# fonte_chaveada.net
KiCad netlist of a schematic drawn in Altium Designer
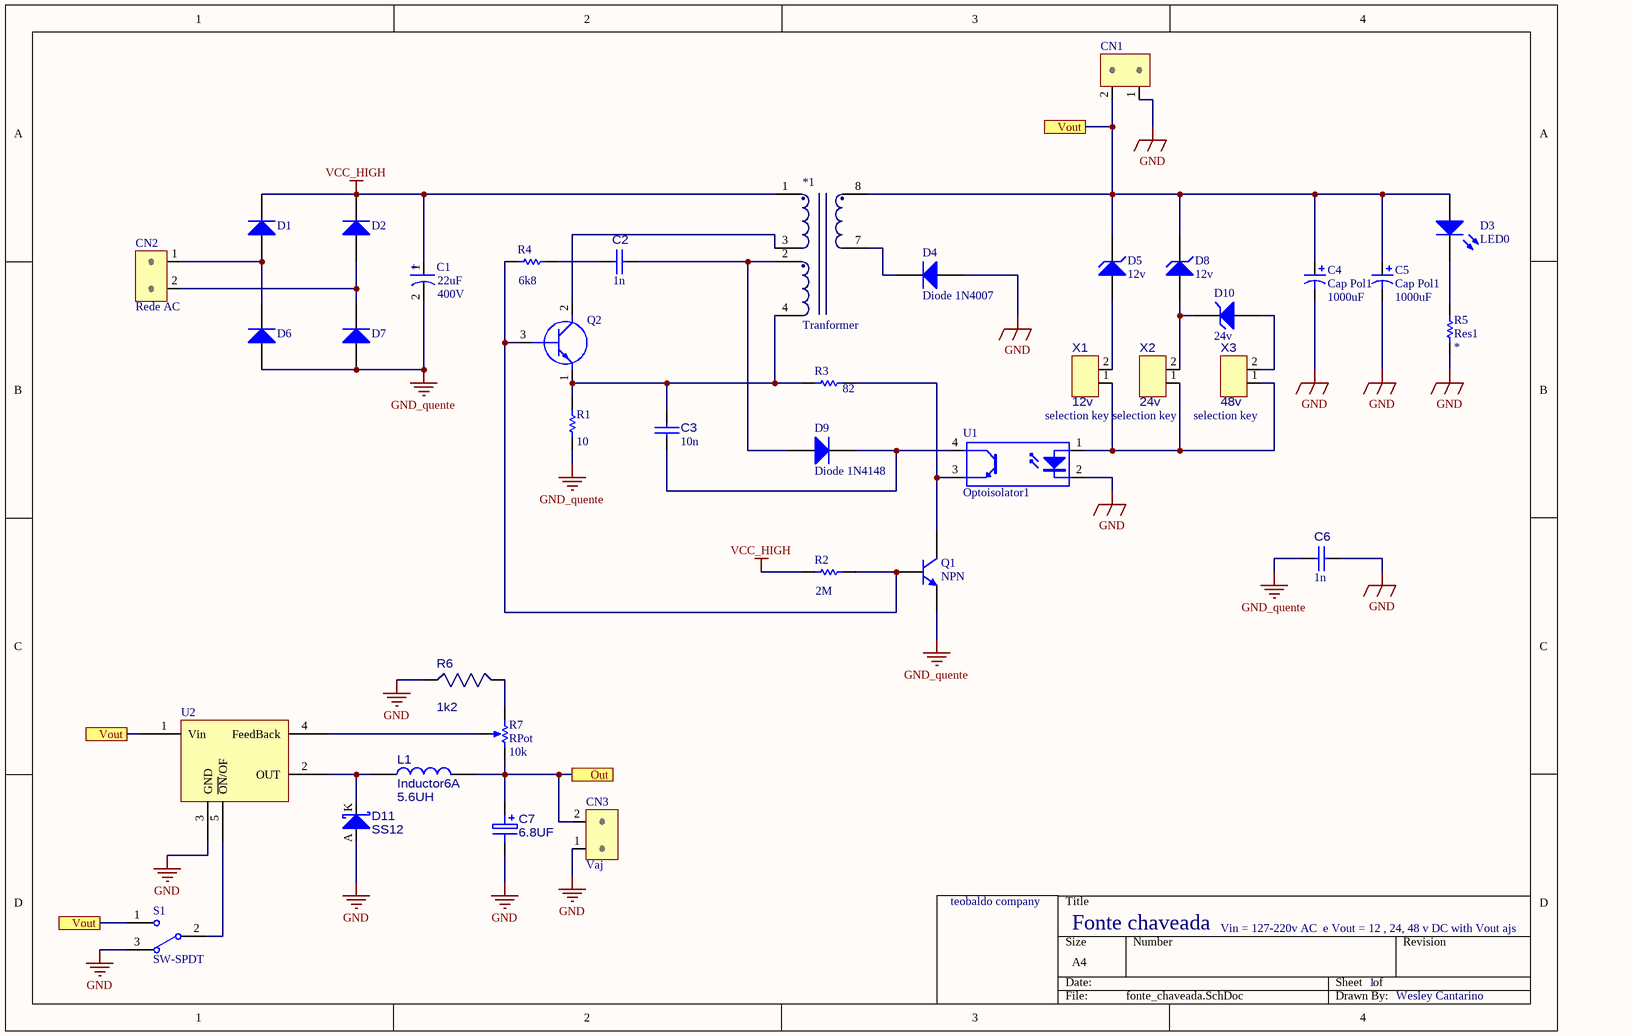
[diagram p0: fonte_chaveada.SchDoc]

(export (version "E")
  (design (tool "Eeschema 10.0.6"))
  (components
    (comp (ref "*1")
      (value "Tranformer")
      (footprint "DIV_TRAFO PLC")
      (libsource (lib "i9Library_Altium") (part "Tranformer PLC"))
    )
    (comp (ref "C1")
      (value "22uF")
      (footprint "CAP_ALU_RADIAL_7.5mm")
      (description "PTH Radial Electrolytic Capacitor")
      (fields (field (name "TENSÃO") "400V") (field (name "Comment") "Electrolytic Capacitor"))
      (libsource (lib "i9Library_Altium") (part "CAP_ALU_RADIAL_7.5MM"))
    )
    (comp (ref "C2")
      (value "1n")
      (footprint "CAP_CER_RADIAL_3.5MM")
      (description "PTH Radial Ceramic Capacitor")
      (libsource (lib "i9Library_Altium") (part "CAP_CER_RADIAL_3.5MM"))
    )
    (comp (ref "C3")
      (value "10n")
      (footprint "CAP_CER_RADIAL_3.5MM")
      (description "PTH Radial Ceramic Capacitor")
      (libsource (lib "i9Library_Altium") (part "CAP_CER_RADIAL_3.5MM"))
    )
    (comp (ref "C4")
      (value "Cap Pol1")
      (footprint "RB7.6-15")
      (description "Polarized Capacitor (Radial)")
      (fields (field (name "ALTIUM_VALUE") "1000uF") (field (name "PUBLISHER") "Altium Limited"))
      (libsource (lib "Miscellaneous Devices") (part "Cap Pol1"))
    )
    (comp (ref "C5")
      (value "Cap Pol1")
      (footprint "RB7.6-15")
      (description "Polarized Capacitor (Radial)")
      (fields (field (name "ALTIUM_VALUE") "1000uF") (field (name "PUBLISHER") "Altium Limited"))
      (libsource (lib "Miscellaneous Devices") (part "Cap Pol1"))
    )
    (comp (ref "C6")
      (value "1n")
      (footprint "CAP_CER_RADIAL_3.5MM")
      (description "PTH Radial Ceramic Capacitor")
      (libsource (lib "i9Library_Altium") (part "CAP_CER_RADIAL_3.5MM"))
    )
    (comp (ref "C7")
      (value "6.8UF")
      (footprint "RADPOL8X11")
      (libsource (lib "i9Library_v1.7.5") (part "ELECTRO1_1"))
    )
    (comp (ref "CN1")
      (value "Vout")
      (footprint "MKDSN02")
      (description "MKDS")
      (libsource (lib "") (part "CN_2_1"))
    )
    (comp (ref "CN2")
      (value "Rede AC")
      (footprint "MKDSN02")
      (description "MKDS")
      (libsource (lib "i9Library_v1.7.5") (part "CN_2"))
    )
    (comp (ref "CN3")
      (value "Vaj")
      (footprint "CN_KRE_2")
      (description "MKDS_2")
      (libsource (lib "i9Library_Altium") (part "CN_MKDS_2"))
    )
    (comp (ref "D1")
      (value "Diode 1N4007")
      (footprint "DO-41")
      (description "1 Amp General Purpose Rectifier")
      (fields (field (name "PUBLISHER") "Altium Limited"))
      (libsource (lib "Miscellaneous Devices") (part "Diode 1N4007"))
    )
    (comp (ref "D2")
      (value "Diode 1N4007")
      (footprint "DO-41")
      (description "1 Amp General Purpose Rectifier")
      (fields (field (name "PUBLISHER") "Altium Limited"))
      (libsource (lib "Miscellaneous Devices") (part "Diode 1N4007"))
    )
    (comp (ref "D3")
      (value "LED0")
      (footprint "LED-0")
      (description "Typical INFRARED GaAs LED")
      (fields (field (name "PUBLISHER") "Altium Limited"))
      (libsource (lib "Miscellaneous Devices") (part "LED0"))
    )
    (comp (ref "D4")
      (value "Diode 1N4007")
      (footprint "DO-41")
      (description "1 Amp General Purpose Rectifier")
      (fields (field (name "PUBLISHER") "Altium Limited"))
      (libsource (lib "Miscellaneous Devices") (part "Diode 1N4007"))
    )
    (comp (ref "D5")
      (value "12v")
      (footprint "DIO_PTH_5MM")
      (description "Zener Diode")
      (fields (field (name "PUBLISHER") "Altium Limited"))
      (libsource (lib "Miscellaneous Devices") (part "D Zener"))
    )
    (comp (ref "D6")
      (value "Diode 1N4007")
      (footprint "DO-41")
      (description "1 Amp General Purpose Rectifier")
      (fields (field (name "PUBLISHER") "Altium Limited"))
      (libsource (lib "Miscellaneous Devices") (part "Diode 1N4007"))
    )
    (comp (ref "D7")
      (value "Diode 1N4007")
      (footprint "DO-41")
      (description "1 Amp General Purpose Rectifier")
      (fields (field (name "PUBLISHER") "Altium Limited"))
      (libsource (lib "Miscellaneous Devices") (part "Diode 1N4007"))
    )
    (comp (ref "D8")
      (value "12v")
      (footprint "DIO_PTH_5MM")
      (description "Zener Diode")
      (fields (field (name "PUBLISHER") "Altium Limited"))
      (libsource (lib "Miscellaneous Devices") (part "D Zener"))
    )
    (comp (ref "D9")
      (value "Diode 1N4148")
      (footprint "DO-41")
      (description "1 Amp General Purpose Rectifier")
      (fields (field (name "PUBLISHER") "Altium Limited"))
      (libsource (lib "Miscellaneous Devices") (part "Diode 1N4007"))
    )
    (comp (ref "D10")
      (value "24v")
      (footprint "DIO_PTH_5MM")
      (description "Zener Diode")
      (fields (field (name "PUBLISHER") "Altium Limited"))
      (libsource (lib "Miscellaneous Devices") (part "D Zener"))
    )
    (comp (ref "D11")
      (value "SS12")
      (footprint "DIO_PTH_5MM")
      (description "Schottky Diode")
      (fields
        (field (name "DIGIKEY PART NUMBER") "SS12E-TPMSCT-ND")
        (field (name "Comment") "DIODE - SCHOTTKY")
      )
      (libsource (lib "i9Library_v1.7.5") (part "DIODE - SCHOTTKY"))
    )
    (comp (ref "L1")
      (value "5.6UH")
      (footprint "Inductor6A")
      (description "FIXED IND 5.6UH 6A 14.4 MOHM SMD")
      (libsource (lib "i9Library_v1.7.5") (part "IND_1"))
    )
    (comp (ref "Q1")
      (value "NPN")
      (footprint "TO-226-AA")
      (description "NPN Bipolar Transistor")
      (fields (field (name "PUBLISHER") "Altium Limited"))
      (libsource (lib "Miscellaneous Devices") (part "NPN"))
    )
    (comp (ref "Q2")
      (value "BD135")
      (footprint "SamacSys:TO239P266X762X1345-3P")
      (description "Transistor BJT NPN")
      (fields (field (name "MOUSER PART NUMBER") "863-BD135") (field (name "RS PART NUMBER") "3489490"))
      (libsource (lib "*") (part "BD135"))
    )
    (comp (ref "R1")
      (value "10")
      (footprint "AXIAL-0.3")
      (description "Resistor")
      (fields (field (name "Comment") "Res1") (field (name "PUBLISHER") "Altium Limited"))
      (libsource (lib "Miscellaneous Devices") (part "Res1"))
    )
    (comp (ref "R2")
      (value "2M")
      (footprint "AXIAL-0.3")
      (description "Resistor")
      (fields (field (name "Comment") "Res1") (field (name "PUBLISHER") "Altium Limited"))
      (libsource (lib "Miscellaneous Devices") (part "Res1"))
    )
    (comp (ref "R3")
      (value "82")
      (footprint "AXIAL-0.3")
      (description "Resistor")
      (fields (field (name "Comment") "Res1") (field (name "PUBLISHER") "Altium Limited"))
      (libsource (lib "Miscellaneous Devices") (part "Res1"))
    )
    (comp (ref "R4")
      (value "6k8")
      (footprint "AXIAL-0.3")
      (description "Resistor")
      (fields (field (name "Comment") "Res1") (field (name "PUBLISHER") "Altium Limited"))
      (libsource (lib "Miscellaneous Devices") (part "Res1"))
    )
    (comp (ref "R5")
      (value "Res1")
      (footprint "AXIAL-0.3")
      (description "Resistor")
      (fields (field (name "ALTIUM_VALUE") "*") (field (name "PUBLISHER") "Altium Limited"))
      (libsource (lib "Miscellaneous Devices") (part "Res1"))
    )
    (comp (ref "R6")
      (value "1k2")
      (footprint "RES-7.62mm")
      (description "Pin Through Hole Resistor 300mils/7.62mm")
      (libsource (lib "i9Library_v1.7.5") (part "RES_PTH300"))
    )
    (comp (ref "R7")
      (value "RPot")
      (footprint "CN_KRE_3")
      (description "Potentiometer")
      (fields (field (name "ALTIUM_VALUE") "10k") (field (name "PUBLISHER") "Altium Limited"))
      (libsource (lib "Miscellaneous Devices") (part "RPot"))
    )
    (comp (ref "S1")
      (value "SW-SPDT")
      (footprint "Pin Header 3 Ways")
      (description "SPDT Subminiature Toggle Switch, Right Angle Mounting, Vertical Actuation")
      (fields (field (name "PUBLISHER") "Altium Limited"))
      (libsource (lib "Miscellaneous Devices") (part "SW-SPDT"))
    )
    (comp (ref "U1")
      (value "Optoisolator1")
      (footprint "DIP-4")
      (description "4-Pin Phototransistor Optocoupler")
      (fields (field (name "PUBLISHER") "Altium Limited"))
      (libsource (lib "Miscellaneous Devices") (part "Optoisolator1"))
    )
    (comp (ref "U2")
      (value "LM2576HV 5.0")
      (footprint "LM2576-TO220")
      (libsource (lib "i9Library_v1.7.5") (part "LM2576"))
    )
    (comp (ref "X1")
      (value "selection key")
      (footprint "12v")
      (description "1X2")
      (libsource (lib "i9Library_Altium") (part "HEADER_1X2"))
    )
    (comp (ref "X2")
      (value "selection key")
      (footprint "24v")
      (description "1X2")
      (libsource (lib "i9Library_Altium") (part "HEADER_1X2"))
    )
    (comp (ref "X3")
      (value "selection key")
      (footprint "48v")
      (description "1X2")
      (libsource (lib "i9Library_Altium") (part "HEADER_1X2"))
    )
  )
  (nets
    (net (code "1") (name "/Out") (class "Default")
      (node (ref "C7") (pin "1") (pintype "passive"))
      (node (ref "CN3") (pin "2") (pinfunction "2_2") (pintype "passive"))
      (node (ref "L1") (pin "2") (pinfunction "2_2") (pintype "passive"))
      (node (ref "R7") (pin "2") (pinfunction "BOT_2") (pintype "passive"))
    )
    (net (code "2") (name "/Vout") (class "Default")
      (node (ref "*1") (pin "8") (pinfunction "8_8") (pintype "passive"))
      (node (ref "C4") (pin "1") (pinfunction "1_1") (pintype "passive"))
      (node (ref "C5") (pin "1") (pinfunction "1_1") (pintype "passive"))
      (node (ref "CN1") (pin "2") (pinfunction "2_2") (pintype "passive"))
      (node (ref "D3") (pin "1") (pinfunction "A_1") (pintype "passive"))
      (node (ref "D5") (pin "2") (pinfunction "K_2") (pintype "passive"))
      (node (ref "D8") (pin "2") (pinfunction "K_2") (pintype "passive"))
      (node (ref "S1") (pin "1") (pinfunction "1_1") (pintype "passive"))
      (node (ref "U2") (pin "1") (pinfunction "Vin_1") (pintype "passive"))
    )
    (net (code "3") (name "GND") (class "Default")
      (node (ref "C4") (pin "2") (pinfunction "2_2") (pintype "passive"))
      (node (ref "C5") (pin "2") (pinfunction "2_2") (pintype "passive"))
      (node (ref "C6") (pin "1") (pintype "passive"))
      (node (ref "C7") (pin "2") (pintype "passive"))
      (node (ref "CN1") (pin "1") (pintype "passive"))
      (node (ref "CN3") (pin "1") (pintype "passive"))
      (node (ref "D11") (pin "A") (pinfunction "A_A") (pintype "passive"))
      (node (ref "D4") (pin "1") (pinfunction "A_1") (pintype "passive"))
      (node (ref "R5") (pin "1") (pinfunction "1_1") (pintype "passive"))
      (node (ref "R6") (pin "1") (pintype "passive"))
      (node (ref "S1") (pin "3") (pinfunction "3_3") (pintype "passive"))
      (node (ref "U1") (pin "2") (pinfunction "K_2") (pintype "passive"))
      (node (ref "U2") (pin "3") (pinfunction "GND_3") (pintype "passive"))
    )
    (net (code "4") (name "GND_quente") (class "Default")
      (node (ref "C1") (pin "2") (pintype "passive"))
      (node (ref "C6") (pin "2") (pintype "passive"))
      (node (ref "D6") (pin "1") (pinfunction "A_1") (pintype "passive"))
      (node (ref "D7") (pin "1") (pinfunction "A_1") (pintype "passive"))
      (node (ref "Q1") (pin "3") (pinfunction "E_3") (pintype "passive"))
      (node (ref "R1") (pin "2") (pinfunction "2_2") (pintype "passive"))
    )
    (net (code "5") (name "Net-(C2-Pad1)") (class "Default")
      (node (ref "C2") (pin "1") (pintype "passive"))
      (node (ref "R4") (pin "2") (pinfunction "2_2") (pintype "passive"))
    )
    (net (code "6") (name "Net-(D1-A)") (class "Default")
      (node (ref "CN2") (pin "1") (pintype "passive"))
      (node (ref "D1") (pin "1") (pinfunction "A_1") (pintype "passive"))
      (node (ref "D6") (pin "2") (pinfunction "K_2") (pintype "passive"))
    )
    (net (code "7") (name "Net-(D2-A)") (class "Default")
      (node (ref "CN2") (pin "2") (pinfunction "2_2") (pintype "passive"))
      (node (ref "D2") (pin "1") (pinfunction "A_1") (pintype "passive"))
      (node (ref "D7") (pin "2") (pinfunction "K_2") (pintype "passive"))
    )
    (net (code "8") (name "Net-(D3-K)") (class "Default")
      (node (ref "D3") (pin "2") (pinfunction "K_2") (pintype "passive"))
      (node (ref "R5") (pin "2") (pinfunction "2_2") (pintype "passive"))
    )
    (net (code "9") (name "Net-(D4-K)") (class "Default")
      (node (ref "*1") (pin "7") (pinfunction "7_7") (pintype "passive"))
      (node (ref "D4") (pin "2") (pinfunction "K_2") (pintype "passive"))
    )
    (net (code "10") (name "Net-(D5-A)") (class "Default")
      (node (ref "D5") (pin "1") (pinfunction "A_1") (pintype "passive"))
      (node (ref "X1") (pin "2") (pinfunction "2_2") (pintype "passive"))
    )
    (net (code "11") (name "Net-(D9-A)") (class "Default")
      (node (ref "*1") (pin "2") (pinfunction "2_2") (pintype "passive"))
      (node (ref "C2") (pin "2") (pintype "passive"))
      (node (ref "D9") (pin "1") (pinfunction "A_1") (pintype "passive"))
    )
    (net (code "12") (name "Net-(D9-K)") (class "Default")
      (node (ref "C3") (pin "1") (pintype "passive"))
      (node (ref "D9") (pin "2") (pinfunction "K_2") (pintype "passive"))
      (node (ref "U1") (pin "4") (pinfunction "C_4") (pintype "passive"))
    )
    (net (code "13") (name "Net-(D10-A)") (class "Default")
      (node (ref "D10") (pin "1") (pinfunction "A_1") (pintype "passive"))
      (node (ref "X3") (pin "2") (pinfunction "2_2") (pintype "passive"))
    )
    (net (code "14") (name "Net-(D10-K)") (class "Default")
      (node (ref "D10") (pin "2") (pinfunction "K_2") (pintype "passive"))
      (node (ref "D8") (pin "1") (pinfunction "A_1") (pintype "passive"))
      (node (ref "X2") (pin "2") (pinfunction "2_2") (pintype "passive"))
    )
    (net (code "15") (name "Net-(Q1-B)") (class "Default")
      (node (ref "Q1") (pin "2") (pinfunction "B_2") (pintype "passive"))
      (node (ref "Q2") (pin "3") (pinfunction "B_3") (pintype "passive"))
      (node (ref "R2") (pin "1") (pinfunction "1_1") (pintype "passive"))
      (node (ref "R4") (pin "1") (pinfunction "1_1") (pintype "passive"))
    )
    (net (code "16") (name "Net-(Q1-C)") (class "Default")
      (node (ref "Q1") (pin "1") (pinfunction "C_1") (pintype "passive"))
      (node (ref "R3") (pin "1") (pinfunction "1_1") (pintype "passive"))
      (node (ref "U1") (pin "3") (pinfunction "E_3") (pintype "passive"))
    )
    (net (code "17") (name "Net-(Q2-C)") (class "Default")
      (node (ref "*1") (pin "3") (pinfunction "3_3") (pintype "passive"))
      (node (ref "Q2") (pin "2") (pinfunction "C_2") (pintype "passive"))
    )
    (net (code "18") (name "Net-(Q2-E)") (class "Default")
      (node (ref "*1") (pin "4") (pinfunction "4_4") (pintype "passive"))
      (node (ref "C3") (pin "2") (pintype "passive"))
      (node (ref "Q2") (pin "1") (pinfunction "E_1") (pintype "passive"))
      (node (ref "R1") (pin "1") (pinfunction "1_1") (pintype "passive"))
      (node (ref "R3") (pin "2") (pinfunction "2_2") (pintype "passive"))
    )
    (net (code "19") (name "Net-(R7-TAP)") (class "Default")
      (node (ref "R7") (pin "3") (pinfunction "TAP_3") (pintype "passive"))
      (node (ref "U2") (pin "4") (pinfunction "FeedBack_4") (pintype "passive"))
    )
    (net (code "20") (name "Net-(R7-TOP)") (class "Default")
      (node (ref "R6") (pin "2") (pintype "passive"))
      (node (ref "R7") (pin "1") (pinfunction "TOP_1") (pintype "passive"))
    )
    (net (code "21") (name "Net-(U1-A)") (class "Default")
      (node (ref "U1") (pin "1") (pinfunction "A_1") (pintype "passive"))
      (node (ref "X1") (pin "1") (pinfunction "1_1") (pintype "passive"))
      (node (ref "X2") (pin "1") (pinfunction "1_1") (pintype "passive"))
      (node (ref "X3") (pin "1") (pinfunction "1_1") (pintype "passive"))
    )
    (net (code "22") (name "Net-(U2-OUT)") (class "Default")
      (node (ref "D11") (pin "K") (pinfunction "K_K") (pintype "passive"))
      (node (ref "L1") (pin "1") (pinfunction "1_1") (pintype "passive"))
      (node (ref "U2") (pin "2") (pinfunction "OUT_2") (pintype "passive"))
    )
    (net (code "23") (name "Net-(U2-~{ON}{slash}OF)") (class "Default")
      (node (ref "S1") (pin "2") (pinfunction "2_2") (pintype "passive"))
      (node (ref "U2") (pin "5") (pinfunction "~{ON}/OF_5") (pintype "passive"))
    )
    (net (code "24") (name "VCC_HIGH") (class "Default")
      (node (ref "*1") (pin "1") (pinfunction "1_1") (pintype "passive"))
      (node (ref "C1") (pin "1") (pinfunction "1_1") (pintype "passive"))
      (node (ref "D1") (pin "2") (pinfunction "K_2") (pintype "passive"))
      (node (ref "D2") (pin "2") (pinfunction "K_2") (pintype "passive"))
      (node (ref "R2") (pin "2") (pinfunction "2_2") (pintype "passive"))
    )
  )
)
